# drive.net
KiCad netlist of a schematic drawn in Altium Designer
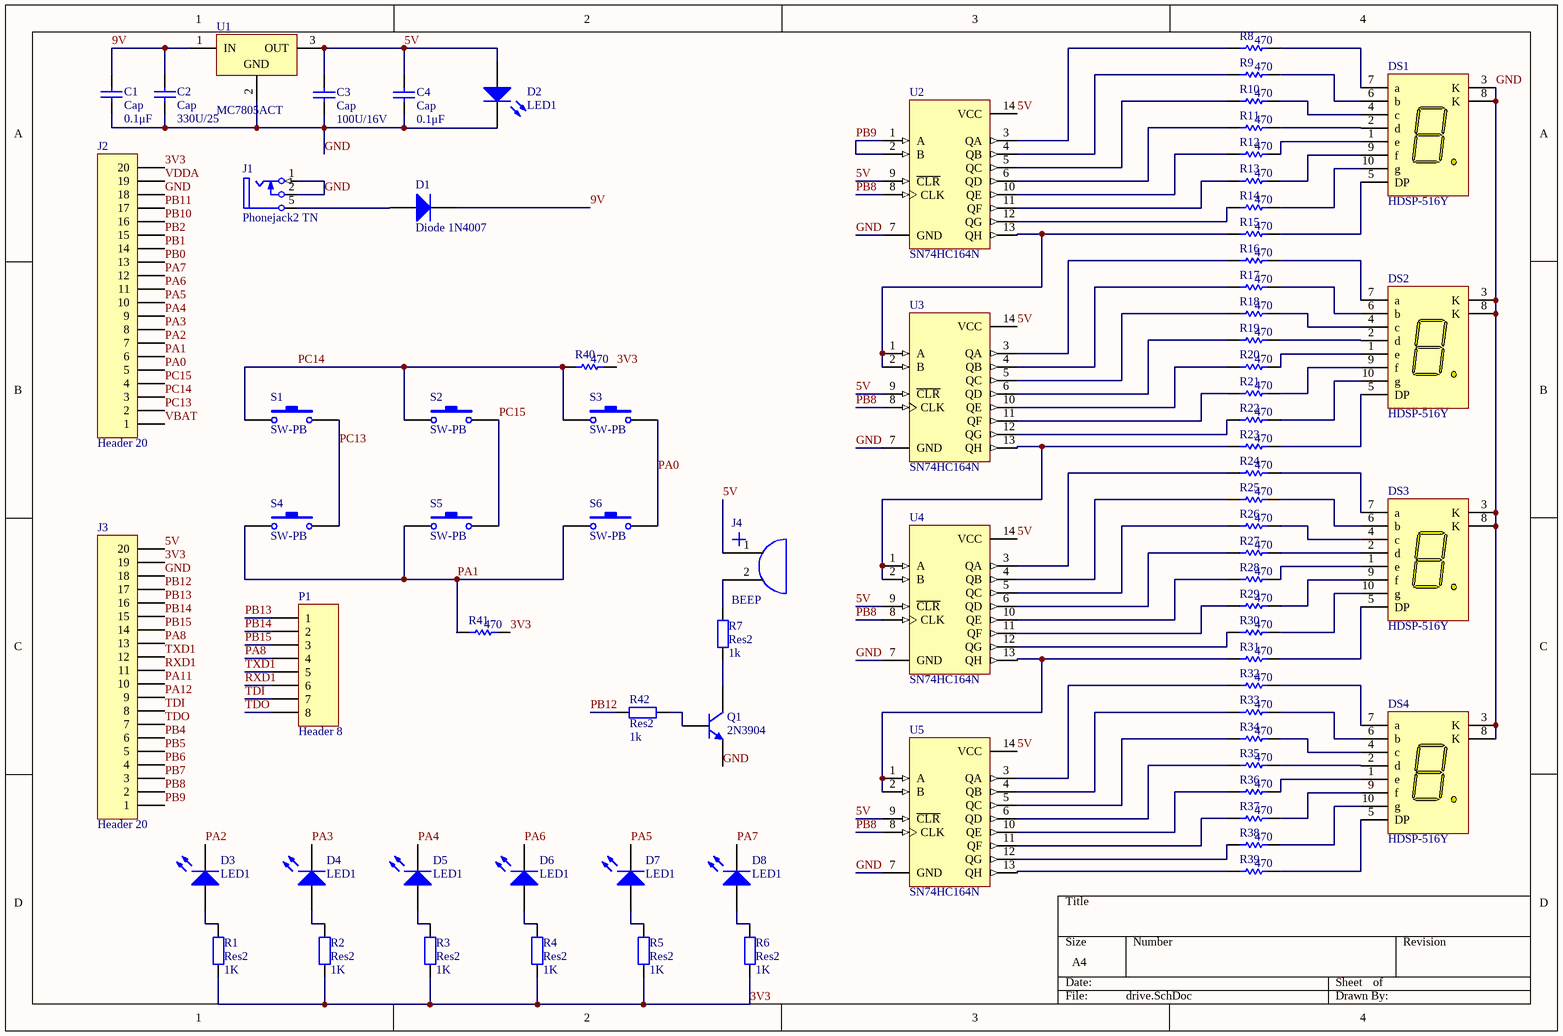
[diagram p0: drive.SchDoc]

(export (version "E")
  (design (tool "Eeschema 10.0.6"))
  (components
    (comp (ref "C1")
      (value "Cap")
      (footprint "RAD-0.3")
      (description "Capacitor")
      (fields (field (name "ALTIUM_VALUE") "0.1μF") (field (name "PUBLISHER") "Altium Limited"))
      (libsource (lib "Miscellaneous Devices") (part "Cap"))
    )
    (comp (ref "C2")
      (value "Cap")
      (footprint "RAD-0.3")
      (description "Capacitor")
      (fields (field (name "ALTIUM_VALUE") "330U/25") (field (name "PUBLISHER") "Altium Limited"))
      (libsource (lib "Miscellaneous Devices") (part "Cap"))
    )
    (comp (ref "C3")
      (value "Cap")
      (footprint "RAD-0.3")
      (description "Capacitor")
      (fields (field (name "ALTIUM_VALUE") "100U/16V") (field (name "PUBLISHER") "Altium Limited"))
      (libsource (lib "Miscellaneous Devices") (part "Cap"))
    )
    (comp (ref "C4")
      (value "Cap")
      (footprint "RAD-0.3")
      (description "Capacitor")
      (fields (field (name "ALTIUM_VALUE") "0.1μF") (field (name "PUBLISHER") "Altium Limited"))
      (libsource (lib "Miscellaneous Devices") (part "Cap"))
    )
    (comp (ref "D1")
      (value "Diode 1N4007")
      (footprint "DO-41")
      (description "1 Amp General Purpose Rectifier")
      (fields (field (name "PUBLISHER") "Altium Limited"))
      (libsource (lib "Miscellaneous Devices") (part "Diode 1N4007"))
    )
    (comp (ref "D2")
      (value "LED1")
      (footprint "LED-1")
      (description "Typical RED GaAs LED")
      (fields (field (name "PUBLISHER") "Altium Limited"))
      (libsource (lib "Miscellaneous Devices") (part "LED1"))
    )
    (comp (ref "D3")
      (value "LED1")
      (footprint "LED-1")
      (description "Typical RED GaAs LED")
      (fields (field (name "PUBLISHER") "Altium Limited"))
      (libsource (lib "Miscellaneous Devices") (part "LED1"))
    )
    (comp (ref "D4")
      (value "LED1")
      (footprint "LED-1")
      (description "Typical RED GaAs LED")
      (fields (field (name "PUBLISHER") "Altium Limited"))
      (libsource (lib "Miscellaneous Devices") (part "LED1"))
    )
    (comp (ref "D5")
      (value "LED1")
      (footprint "LED-1")
      (description "Typical RED GaAs LED")
      (fields (field (name "PUBLISHER") "Altium Limited"))
      (libsource (lib "Miscellaneous Devices") (part "LED1"))
    )
    (comp (ref "D6")
      (value "LED1")
      (footprint "LED-1")
      (description "Typical RED GaAs LED")
      (fields (field (name "PUBLISHER") "Altium Limited"))
      (libsource (lib "Miscellaneous Devices") (part "LED1"))
    )
    (comp (ref "D7")
      (value "LED1")
      (footprint "LED-1")
      (description "Typical RED GaAs LED")
      (fields (field (name "PUBLISHER") "Altium Limited"))
      (libsource (lib "Miscellaneous Devices") (part "LED1"))
    )
    (comp (ref "D8")
      (value "LED1")
      (footprint "LED-1")
      (description "Typical RED GaAs LED")
      (fields (field (name "PUBLISHER") "Altium Limited"))
      (libsource (lib "Miscellaneous Devices") (part "LED1"))
    )
    (comp (ref "DS1")
      (value "HDSP-516Y")
      (footprint "Case-5")
      (description "13 mm Slim Font, Standard Current, Yellow 7-Segment Display: CC, RH DP")
      (fields (field (name "PUBLISHER") "Altium Limited"))
      (libsource (lib "Agilent LED Display 7-Segment, 1-Digit") (part "HDSP-516Y"))
    )
    (comp (ref "DS2")
      (value "HDSP-516Y")
      (footprint "Case-5")
      (description "13 mm Slim Font, Standard Current, Yellow 7-Segment Display: CC, RH DP")
      (fields (field (name "PUBLISHER") "Altium Limited"))
      (libsource (lib "Agilent LED Display 7-Segment, 1-Digit") (part "HDSP-516Y"))
    )
    (comp (ref "DS3")
      (value "HDSP-516Y")
      (footprint "Case-5")
      (description "13 mm Slim Font, Standard Current, Yellow 7-Segment Display: CC, RH DP")
      (fields (field (name "PUBLISHER") "Altium Limited"))
      (libsource (lib "Agilent LED Display 7-Segment, 1-Digit") (part "HDSP-516Y"))
    )
    (comp (ref "DS4")
      (value "HDSP-516Y")
      (footprint "Case-5")
      (description "13 mm Slim Font, Standard Current, Yellow 7-Segment Display: CC, RH DP")
      (fields (field (name "PUBLISHER") "Altium Limited"))
      (libsource (lib "Agilent LED Display 7-Segment, 1-Digit") (part "HDSP-516Y"))
    )
    (comp (ref "J1")
      (value "Phonejack2 TN")
      (footprint "DC-005")
      (description "Jack Socket, 1/4\" [6.5mm], Thru-Hole, Vertical, 2-Conductor with Tip closed")
      (fields (field (name "PUBLISHER") "Altium Limited"))
      (libsource (lib "Miscellaneous Connectors") (part "Phonejack2 TN"))
    )
    (comp (ref "J2")
      (value "Header 20")
      (footprint "HDR1X20")
      (description "Header, 20-Pin")
      (fields (field (name "PUBLISHER") "Altium Limited"))
      (libsource (lib "Miscellaneous Connectors") (part "Header 20"))
    )
    (comp (ref "J3")
      (value "Header 20")
      (footprint "HDR1X20")
      (description "Header, 20-Pin")
      (fields (field (name "PUBLISHER") "Altium Limited"))
      (libsource (lib "Miscellaneous Connectors") (part "Header 20"))
    )
    (comp (ref "J4")
      (value "BEEP")
      (footprint "Beep")
      (description "蜂鸣器")
      (libsource (lib "TSLone") (part "BEEP"))
    )
    (comp (ref "P1")
      (value "Header 8")
      (footprint "HDR1X8")
      (description "Header, 8-Pin")
      (fields (field (name "PUBLISHER") "Altium Limited"))
      (libsource (lib "Miscellaneous Connectors") (part "Header 8"))
    )
    (comp (ref "Q1")
      (value "2N3904")
      (footprint "TO-92A")
      (description "NPN General Purpose Amplifier")
      (fields (field (name "PUBLISHER") "Altium Limited"))
      (libsource (lib "Miscellaneous Devices") (part "2N3904"))
    )
    (comp (ref "R1")
      (value "Res2")
      (footprint "AXIAL-0.4")
      (description "Resistor")
      (fields (field (name "ALTIUM_VALUE") "1K") (field (name "PUBLISHER") "Altium Limited"))
      (libsource (lib "Miscellaneous Devices") (part "Res2"))
    )
    (comp (ref "R2")
      (value "Res2")
      (footprint "AXIAL-0.4")
      (description "Resistor")
      (fields (field (name "ALTIUM_VALUE") "1K") (field (name "PUBLISHER") "Altium Limited"))
      (libsource (lib "Miscellaneous Devices") (part "Res2"))
    )
    (comp (ref "R3")
      (value "Res2")
      (footprint "AXIAL-0.4")
      (description "Resistor")
      (fields (field (name "ALTIUM_VALUE") "1K") (field (name "PUBLISHER") "Altium Limited"))
      (libsource (lib "Miscellaneous Devices") (part "Res2"))
    )
    (comp (ref "R4")
      (value "Res2")
      (footprint "AXIAL-0.4")
      (description "Resistor")
      (fields (field (name "ALTIUM_VALUE") "1K") (field (name "PUBLISHER") "Altium Limited"))
      (libsource (lib "Miscellaneous Devices") (part "Res2"))
    )
    (comp (ref "R5")
      (value "Res2")
      (footprint "AXIAL-0.4")
      (description "Resistor")
      (fields (field (name "ALTIUM_VALUE") "1K") (field (name "PUBLISHER") "Altium Limited"))
      (libsource (lib "Miscellaneous Devices") (part "Res2"))
    )
    (comp (ref "R6")
      (value "Res2")
      (footprint "AXIAL-0.4")
      (description "Resistor")
      (fields (field (name "ALTIUM_VALUE") "1K") (field (name "PUBLISHER") "Altium Limited"))
      (libsource (lib "Miscellaneous Devices") (part "Res2"))
    )
    (comp (ref "R7")
      (value "Res2")
      (footprint "AXIAL-0.4")
      (description "Resistor")
      (fields (field (name "ALTIUM_VALUE") "1k") (field (name "PUBLISHER") "Altium Limited"))
      (libsource (lib "Miscellaneous Devices") (part "Res2"))
    )
    (comp (ref "R8")
      (value "470")
      (footprint "AXIAL-0.3")
      (description "Resistor")
      (fields (field (name "Comment") "Res1") (field (name "PUBLISHER") "Altium Limited"))
      (libsource (lib "Miscellaneous Devices") (part "Res1"))
    )
    (comp (ref "R9")
      (value "470")
      (footprint "AXIAL-0.3")
      (description "Resistor")
      (fields (field (name "Comment") "Res1") (field (name "PUBLISHER") "Altium Limited"))
      (libsource (lib "Miscellaneous Devices") (part "Res1"))
    )
    (comp (ref "R10")
      (value "470")
      (footprint "AXIAL-0.3")
      (description "Resistor")
      (fields (field (name "Comment") "Res1") (field (name "PUBLISHER") "Altium Limited"))
      (libsource (lib "Miscellaneous Devices") (part "Res1"))
    )
    (comp (ref "R11")
      (value "470")
      (footprint "AXIAL-0.3")
      (description "Resistor")
      (fields (field (name "Comment") "Res1") (field (name "PUBLISHER") "Altium Limited"))
      (libsource (lib "Miscellaneous Devices") (part "Res1"))
    )
    (comp (ref "R12")
      (value "470")
      (footprint "AXIAL-0.3")
      (description "Resistor")
      (fields (field (name "Comment") "Res1") (field (name "PUBLISHER") "Altium Limited"))
      (libsource (lib "Miscellaneous Devices") (part "Res1"))
    )
    (comp (ref "R13")
      (value "470")
      (footprint "AXIAL-0.3")
      (description "Resistor")
      (fields (field (name "Comment") "Res1") (field (name "PUBLISHER") "Altium Limited"))
      (libsource (lib "Miscellaneous Devices") (part "Res1"))
    )
    (comp (ref "R14")
      (value "470")
      (footprint "AXIAL-0.3")
      (description "Resistor")
      (fields (field (name "Comment") "Res1") (field (name "PUBLISHER") "Altium Limited"))
      (libsource (lib "Miscellaneous Devices") (part "Res1"))
    )
    (comp (ref "R15")
      (value "470")
      (footprint "AXIAL-0.3")
      (description "Resistor")
      (fields (field (name "Comment") "Res1") (field (name "PUBLISHER") "Altium Limited"))
      (libsource (lib "Miscellaneous Devices") (part "Res1"))
    )
    (comp (ref "R16")
      (value "470")
      (footprint "AXIAL-0.3")
      (description "Resistor")
      (fields (field (name "Comment") "Res1") (field (name "PUBLISHER") "Altium Limited"))
      (libsource (lib "Miscellaneous Devices") (part "Res1"))
    )
    (comp (ref "R17")
      (value "470")
      (footprint "AXIAL-0.3")
      (description "Resistor")
      (fields (field (name "Comment") "Res1") (field (name "PUBLISHER") "Altium Limited"))
      (libsource (lib "Miscellaneous Devices") (part "Res1"))
    )
    (comp (ref "R18")
      (value "470")
      (footprint "AXIAL-0.3")
      (description "Resistor")
      (fields (field (name "Comment") "Res1") (field (name "PUBLISHER") "Altium Limited"))
      (libsource (lib "Miscellaneous Devices") (part "Res1"))
    )
    (comp (ref "R19")
      (value "470")
      (footprint "AXIAL-0.3")
      (description "Resistor")
      (fields (field (name "Comment") "Res1") (field (name "PUBLISHER") "Altium Limited"))
      (libsource (lib "Miscellaneous Devices") (part "Res1"))
    )
    (comp (ref "R20")
      (value "470")
      (footprint "AXIAL-0.3")
      (description "Resistor")
      (fields (field (name "Comment") "Res1") (field (name "PUBLISHER") "Altium Limited"))
      (libsource (lib "Miscellaneous Devices") (part "Res1"))
    )
    (comp (ref "R21")
      (value "470")
      (footprint "AXIAL-0.3")
      (description "Resistor")
      (fields (field (name "Comment") "Res1") (field (name "PUBLISHER") "Altium Limited"))
      (libsource (lib "Miscellaneous Devices") (part "Res1"))
    )
    (comp (ref "R22")
      (value "470")
      (footprint "AXIAL-0.3")
      (description "Resistor")
      (fields (field (name "Comment") "Res1") (field (name "PUBLISHER") "Altium Limited"))
      (libsource (lib "Miscellaneous Devices") (part "Res1"))
    )
    (comp (ref "R23")
      (value "470")
      (footprint "AXIAL-0.3")
      (description "Resistor")
      (fields (field (name "Comment") "Res1") (field (name "PUBLISHER") "Altium Limited"))
      (libsource (lib "Miscellaneous Devices") (part "Res1"))
    )
    (comp (ref "R24")
      (value "470")
      (footprint "AXIAL-0.3")
      (description "Resistor")
      (fields (field (name "Comment") "Res1") (field (name "PUBLISHER") "Altium Limited"))
      (libsource (lib "Miscellaneous Devices") (part "Res1"))
    )
    (comp (ref "R25")
      (value "470")
      (footprint "AXIAL-0.3")
      (description "Resistor")
      (fields (field (name "Comment") "Res1") (field (name "PUBLISHER") "Altium Limited"))
      (libsource (lib "Miscellaneous Devices") (part "Res1"))
    )
    (comp (ref "R26")
      (value "470")
      (footprint "AXIAL-0.3")
      (description "Resistor")
      (fields (field (name "Comment") "Res1") (field (name "PUBLISHER") "Altium Limited"))
      (libsource (lib "Miscellaneous Devices") (part "Res1"))
    )
    (comp (ref "R27")
      (value "470")
      (footprint "AXIAL-0.3")
      (description "Resistor")
      (fields (field (name "Comment") "Res1") (field (name "PUBLISHER") "Altium Limited"))
      (libsource (lib "Miscellaneous Devices") (part "Res1"))
    )
    (comp (ref "R28")
      (value "470")
      (footprint "AXIAL-0.3")
      (description "Resistor")
      (fields (field (name "Comment") "Res1") (field (name "PUBLISHER") "Altium Limited"))
      (libsource (lib "Miscellaneous Devices") (part "Res1"))
    )
    (comp (ref "R29")
      (value "470")
      (footprint "AXIAL-0.3")
      (description "Resistor")
      (fields (field (name "Comment") "Res1") (field (name "PUBLISHER") "Altium Limited"))
      (libsource (lib "Miscellaneous Devices") (part "Res1"))
    )
    (comp (ref "R30")
      (value "470")
      (footprint "AXIAL-0.3")
      (description "Resistor")
      (fields (field (name "Comment") "Res1") (field (name "PUBLISHER") "Altium Limited"))
      (libsource (lib "Miscellaneous Devices") (part "Res1"))
    )
    (comp (ref "R31")
      (value "470")
      (footprint "AXIAL-0.3")
      (description "Resistor")
      (fields (field (name "Comment") "Res1") (field (name "PUBLISHER") "Altium Limited"))
      (libsource (lib "Miscellaneous Devices") (part "Res1"))
    )
    (comp (ref "R32")
      (value "470")
      (footprint "AXIAL-0.3")
      (description "Resistor")
      (fields (field (name "Comment") "Res1") (field (name "PUBLISHER") "Altium Limited"))
      (libsource (lib "Miscellaneous Devices") (part "Res1"))
    )
    (comp (ref "R33")
      (value "470")
      (footprint "AXIAL-0.3")
      (description "Resistor")
      (fields (field (name "Comment") "Res1") (field (name "PUBLISHER") "Altium Limited"))
      (libsource (lib "Miscellaneous Devices") (part "Res1"))
    )
    (comp (ref "R34")
      (value "470")
      (footprint "AXIAL-0.3")
      (description "Resistor")
      (fields (field (name "Comment") "Res1") (field (name "PUBLISHER") "Altium Limited"))
      (libsource (lib "Miscellaneous Devices") (part "Res1"))
    )
    (comp (ref "R35")
      (value "470")
      (footprint "AXIAL-0.3")
      (description "Resistor")
      (fields (field (name "Comment") "Res1") (field (name "PUBLISHER") "Altium Limited"))
      (libsource (lib "Miscellaneous Devices") (part "Res1"))
    )
    (comp (ref "R36")
      (value "470")
      (footprint "AXIAL-0.3")
      (description "Resistor")
      (fields (field (name "Comment") "Res1") (field (name "PUBLISHER") "Altium Limited"))
      (libsource (lib "Miscellaneous Devices") (part "Res1"))
    )
    (comp (ref "R37")
      (value "470")
      (footprint "AXIAL-0.3")
      (description "Resistor")
      (fields (field (name "Comment") "Res1") (field (name "PUBLISHER") "Altium Limited"))
      (libsource (lib "Miscellaneous Devices") (part "Res1"))
    )
    (comp (ref "R38")
      (value "470")
      (footprint "AXIAL-0.3")
      (description "Resistor")
      (fields (field (name "Comment") "Res1") (field (name "PUBLISHER") "Altium Limited"))
      (libsource (lib "Miscellaneous Devices") (part "Res1"))
    )
    (comp (ref "R39")
      (value "470")
      (footprint "AXIAL-0.3")
      (description "Resistor")
      (fields (field (name "Comment") "Res1") (field (name "PUBLISHER") "Altium Limited"))
      (libsource (lib "Miscellaneous Devices") (part "Res1"))
    )
    (comp (ref "R40")
      (value "470")
      (footprint "AXIAL-0.3")
      (description "Resistor")
      (fields (field (name "Comment") "Res1") (field (name "PUBLISHER") "Altium Limited"))
      (libsource (lib "Miscellaneous Devices") (part "Res1"))
    )
    (comp (ref "R41")
      (value "470")
      (footprint "AXIAL-0.3")
      (description "Resistor")
      (fields (field (name "Comment") "Res1") (field (name "PUBLISHER") "Altium Limited"))
      (libsource (lib "Miscellaneous Devices") (part "Res1"))
    )
    (comp (ref "R42")
      (value "Res2")
      (footprint "AXIAL-0.4")
      (description "Resistor")
      (fields (field (name "ALTIUM_VALUE") "1k") (field (name "PUBLISHER") "Altium Limited"))
      (libsource (lib "") (part "Res2_1"))
    )
    (comp (ref "S1")
      (value "SW-PB")
      (footprint "SW9")
      (description "微动开关")
      (fields (field (name "PUBLISHER") "Altium Limited"))
      (libsource (lib "TSLone") (part "SW-PB"))
    )
    (comp (ref "S2")
      (value "SW-PB")
      (footprint "SW9")
      (description "微动开关")
      (fields (field (name "PUBLISHER") "Altium Limited"))
      (libsource (lib "TSLone") (part "SW-PB"))
    )
    (comp (ref "S3")
      (value "SW-PB")
      (footprint "SW9")
      (description "微动开关")
      (fields (field (name "PUBLISHER") "Altium Limited"))
      (libsource (lib "TSLone") (part "SW-PB"))
    )
    (comp (ref "S4")
      (value "SW-PB")
      (footprint "SW9")
      (description "微动开关")
      (fields (field (name "PUBLISHER") "Altium Limited"))
      (libsource (lib "TSLone") (part "SW-PB"))
    )
    (comp (ref "S5")
      (value "SW-PB")
      (footprint "SW9")
      (description "微动开关")
      (fields (field (name "PUBLISHER") "Altium Limited"))
      (libsource (lib "TSLone") (part "SW-PB"))
    )
    (comp (ref "S6")
      (value "SW-PB")
      (footprint "SW9")
      (description "微动开关")
      (fields (field (name "PUBLISHER") "Altium Limited"))
      (libsource (lib "TSLone") (part "SW-PB"))
    )
    (comp (ref "U1")
      (value "MC7805ACT")
      (footprint "221A-06")
      (description "Three-Terminal Positive Voltage Regulator")
      (fields (field (name "PUBLISHER") "Altium Limited"))
      (libsource (lib "ON Semi Power Mgt Voltage Regulator") (part "MC7805ACT"))
    )
    (comp (ref "U2")
      (value "SN74HC164N")
      (footprint "N014")
      (description "8-Bit Parallel-Out Serial Shift Register")
      (fields (field (name "PUBLISHER") "Altium Limited"))
      (libsource (lib "TI Logic Register") (part "SN74HC164N"))
    )
    (comp (ref "U3")
      (value "SN74HC164N")
      (footprint "N014")
      (description "8-Bit Parallel-Out Serial Shift Register")
      (fields (field (name "PUBLISHER") "Altium Limited"))
      (libsource (lib "TI Logic Register") (part "SN74HC164N"))
    )
    (comp (ref "U4")
      (value "SN74HC164N")
      (footprint "N014")
      (description "8-Bit Parallel-Out Serial Shift Register")
      (fields (field (name "PUBLISHER") "Altium Limited"))
      (libsource (lib "TI Logic Register") (part "SN74HC164N"))
    )
    (comp (ref "U5")
      (value "SN74HC164N")
      (footprint "N014")
      (description "8-Bit Parallel-Out Serial Shift Register")
      (fields (field (name "PUBLISHER") "Altium Limited"))
      (libsource (lib "TI Logic Register") (part "SN74HC164N"))
    )
  )
  (nets
    (net (code "1") (name "/3V3") (class "Default")
      (node (ref "J2") (pin "20") (pinfunction "20_20") (pintype "passive"))
      (node (ref "J3") (pin "19") (pinfunction "19_19") (pintype "passive"))
      (node (ref "R1") (pin "1") (pinfunction "1_1") (pintype "passive"))
      (node (ref "R2") (pin "1") (pinfunction "1_1") (pintype "passive"))
      (node (ref "R3") (pin "1") (pinfunction "1_1") (pintype "passive"))
      (node (ref "R4") (pin "1") (pinfunction "1_1") (pintype "passive"))
      (node (ref "R40") (pin "2") (pinfunction "2_2") (pintype "passive"))
      (node (ref "R41") (pin "2") (pinfunction "2_2") (pintype "passive"))
      (node (ref "R5") (pin "1") (pinfunction "1_1") (pintype "passive"))
      (node (ref "R6") (pin "1") (pinfunction "1_1") (pintype "passive"))
    )
    (net (code "2") (name "/5V") (class "Default")
      (node (ref "C3") (pin "1") (pinfunction "1_1") (pintype "passive"))
      (node (ref "C4") (pin "1") (pinfunction "1_1") (pintype "passive"))
      (node (ref "D2") (pin "1") (pinfunction "A_1") (pintype "passive"))
      (node (ref "J3") (pin "20") (pinfunction "20_20") (pintype "passive"))
      (node (ref "J4") (pin "1") (pinfunction "0_1") (pintype "passive"))
      (node (ref "U1") (pin "3") (pinfunction "OUT_3") (pintype "power_in"))
      (node (ref "U2") (pin "14") (pinfunction "VCC_14") (pintype "power_in"))
      (node (ref "U2") (pin "9") (pinfunction "~{CLR}_9") (pintype "input"))
      (node (ref "U3") (pin "14") (pinfunction "VCC_14") (pintype "power_in"))
      (node (ref "U3") (pin "9") (pinfunction "~{CLR}_9") (pintype "input"))
      (node (ref "U4") (pin "14") (pinfunction "VCC_14") (pintype "power_in"))
      (node (ref "U4") (pin "9") (pinfunction "~{CLR}_9") (pintype "input"))
      (node (ref "U5") (pin "14") (pinfunction "VCC_14") (pintype "power_in"))
      (node (ref "U5") (pin "9") (pinfunction "~{CLR}_9") (pintype "input"))
    )
    (net (code "3") (name "/9V") (class "Default")
      (node (ref "C1") (pin "1") (pinfunction "1_1") (pintype "passive"))
      (node (ref "C2") (pin "1") (pinfunction "1_1") (pintype "passive"))
      (node (ref "D1") (pin "2") (pinfunction "K_2") (pintype "passive"))
      (node (ref "U1") (pin "1") (pinfunction "IN_1") (pintype "power_in"))
    )
    (net (code "4") (name "/GND") (class "Default")
      (node (ref "C1") (pin "2") (pinfunction "2_2") (pintype "passive"))
      (node (ref "C2") (pin "2") (pinfunction "2_2") (pintype "passive"))
      (node (ref "C3") (pin "2") (pinfunction "2_2") (pintype "passive"))
      (node (ref "C4") (pin "2") (pinfunction "2_2") (pintype "passive"))
      (node (ref "D2") (pin "2") (pinfunction "K_2") (pintype "passive"))
      (node (ref "DS1") (pin "3") (pinfunction "K_3") (pintype "passive"))
      (node (ref "DS1") (pin "8") (pinfunction "K_8") (pintype "passive"))
      (node (ref "DS2") (pin "3") (pinfunction "K_3") (pintype "passive"))
      (node (ref "DS2") (pin "8") (pinfunction "K_8") (pintype "passive"))
      (node (ref "DS3") (pin "3") (pinfunction "K_3") (pintype "passive"))
      (node (ref "DS3") (pin "8") (pinfunction "K_8") (pintype "passive"))
      (node (ref "DS4") (pin "3") (pinfunction "K_3") (pintype "passive"))
      (node (ref "DS4") (pin "8") (pinfunction "K_8") (pintype "passive"))
      (node (ref "J1") (pin "1") (pinfunction "T_1") (pintype "input"))
      (node (ref "J1") (pin "2") (pinfunction "TN_2") (pintype "passive"))
      (node (ref "J2") (pin "18") (pinfunction "18_18") (pintype "passive"))
      (node (ref "J3") (pin "18") (pinfunction "18_18") (pintype "passive"))
      (node (ref "Q1") (pin "1") (pinfunction "E_1") (pintype "passive"))
      (node (ref "U1") (pin "2") (pinfunction "GND_2") (pintype "power_in"))
      (node (ref "U2") (pin "7") (pinfunction "GND_7") (pintype "power_in"))
      (node (ref "U3") (pin "7") (pinfunction "GND_7") (pintype "power_in"))
      (node (ref "U4") (pin "7") (pinfunction "GND_7") (pintype "power_in"))
      (node (ref "U5") (pin "7") (pinfunction "GND_7") (pintype "power_in"))
    )
    (net (code "5") (name "/PA0") (class "Default")
      (node (ref "J2") (pin "5") (pinfunction "5_5") (pintype "passive"))
      (node (ref "S3") (pin "2") (pinfunction "2_2") (pintype "passive"))
      (node (ref "S6") (pin "2") (pinfunction "2_2") (pintype "passive"))
    )
    (net (code "6") (name "/PA1") (class "Default")
      (node (ref "J2") (pin "6") (pinfunction "6_6") (pintype "passive"))
      (node (ref "R41") (pin "1") (pinfunction "1_1") (pintype "passive"))
      (node (ref "S4") (pin "1") (pinfunction "1_1") (pintype "passive"))
      (node (ref "S5") (pin "1") (pinfunction "1_1") (pintype "passive"))
      (node (ref "S6") (pin "1") (pinfunction "1_1") (pintype "passive"))
    )
    (net (code "7") (name "/PA2") (class "Default")
      (node (ref "D3") (pin "2") (pinfunction "K_2") (pintype "passive"))
      (node (ref "J2") (pin "7") (pinfunction "7_7") (pintype "passive"))
    )
    (net (code "8") (name "/PA3") (class "Default")
      (node (ref "D4") (pin "2") (pinfunction "K_2") (pintype "passive"))
      (node (ref "J2") (pin "8") (pinfunction "8_8") (pintype "passive"))
    )
    (net (code "9") (name "/PA4") (class "Default")
      (node (ref "D5") (pin "2") (pinfunction "K_2") (pintype "passive"))
      (node (ref "J2") (pin "9") (pinfunction "9_9") (pintype "passive"))
    )
    (net (code "10") (name "/PA5") (class "Default")
      (node (ref "D7") (pin "2") (pinfunction "K_2") (pintype "passive"))
      (node (ref "J2") (pin "10") (pinfunction "10_10") (pintype "passive"))
    )
    (net (code "11") (name "/PA6") (class "Default")
      (node (ref "D6") (pin "2") (pinfunction "K_2") (pintype "passive"))
      (node (ref "J2") (pin "11") (pinfunction "11_11") (pintype "passive"))
    )
    (net (code "12") (name "/PA7") (class "Default")
      (node (ref "D8") (pin "2") (pinfunction "K_2") (pintype "passive"))
      (node (ref "J2") (pin "12") (pinfunction "12_12") (pintype "passive"))
    )
    (net (code "13") (name "/PA8") (class "Default")
      (node (ref "J3") (pin "13") (pinfunction "13_13") (pintype "passive"))
      (node (ref "P1") (pin "4") (pinfunction "4_4") (pintype "passive"))
    )
    (net (code "14") (name "/PA11") (class "Default")
      (node (ref "J3") (pin "10") (pinfunction "10_10") (pintype "passive"))
    )
    (net (code "15") (name "/PA12") (class "Default")
      (node (ref "J3") (pin "9") (pinfunction "9_9") (pintype "passive"))
    )
    (net (code "16") (name "/PB0") (class "Default")
      (node (ref "J2") (pin "13") (pinfunction "13_13") (pintype "passive"))
    )
    (net (code "17") (name "/PB1") (class "Default")
      (node (ref "J2") (pin "14") (pinfunction "14_14") (pintype "passive"))
    )
    (net (code "18") (name "/PB2") (class "Default")
      (node (ref "J2") (pin "15") (pinfunction "15_15") (pintype "passive"))
    )
    (net (code "19") (name "/PB4") (class "Default")
      (node (ref "J3") (pin "6") (pinfunction "6_6") (pintype "passive"))
    )
    (net (code "20") (name "/PB5") (class "Default")
      (node (ref "J3") (pin "5") (pinfunction "5_5") (pintype "passive"))
    )
    (net (code "21") (name "/PB6") (class "Default")
      (node (ref "J3") (pin "4") (pinfunction "4_4") (pintype "passive"))
    )
    (net (code "22") (name "/PB7") (class "Default")
      (node (ref "J3") (pin "3") (pinfunction "3_3") (pintype "passive"))
    )
    (net (code "23") (name "/PB8") (class "Default")
      (node (ref "J3") (pin "2") (pinfunction "2_2") (pintype "passive"))
      (node (ref "U2") (pin "8") (pinfunction "CLK_8") (pintype "input"))
      (node (ref "U3") (pin "8") (pinfunction "CLK_8") (pintype "input"))
      (node (ref "U4") (pin "8") (pinfunction "CLK_8") (pintype "input"))
      (node (ref "U5") (pin "8") (pinfunction "CLK_8") (pintype "input"))
    )
    (net (code "24") (name "/PB9") (class "Default")
      (node (ref "J3") (pin "1") (pinfunction "1_1") (pintype "passive"))
      (node (ref "U2") (pin "1") (pinfunction "A_1") (pintype "input"))
      (node (ref "U2") (pin "2") (pinfunction "B_2") (pintype "input"))
    )
    (net (code "25") (name "/PB10") (class "Default")
      (node (ref "J2") (pin "16") (pinfunction "16_16") (pintype "passive"))
    )
    (net (code "26") (name "/PB11") (class "Default")
      (node (ref "J2") (pin "17") (pinfunction "17_17") (pintype "passive"))
    )
    (net (code "27") (name "/PB12") (class "Default")
      (node (ref "J3") (pin "17") (pinfunction "17_17") (pintype "passive"))
      (node (ref "R42") (pin "2") (pinfunction "2_2") (pintype "passive"))
    )
    (net (code "28") (name "/PB13") (class "Default")
      (node (ref "J3") (pin "16") (pinfunction "16_16") (pintype "passive"))
      (node (ref "P1") (pin "1") (pinfunction "1_1") (pintype "passive"))
    )
    (net (code "29") (name "/PB14") (class "Default")
      (node (ref "J3") (pin "15") (pinfunction "15_15") (pintype "passive"))
      (node (ref "P1") (pin "2") (pinfunction "2_2") (pintype "passive"))
    )
    (net (code "30") (name "/PB15") (class "Default")
      (node (ref "J3") (pin "14") (pinfunction "14_14") (pintype "passive"))
      (node (ref "P1") (pin "3") (pinfunction "3_3") (pintype "passive"))
    )
    (net (code "31") (name "/PC13") (class "Default")
      (node (ref "J2") (pin "2") (pinfunction "2_2") (pintype "passive"))
      (node (ref "S1") (pin "2") (pinfunction "2_2") (pintype "passive"))
      (node (ref "S4") (pin "2") (pinfunction "2_2") (pintype "passive"))
    )
    (net (code "32") (name "/PC14") (class "Default")
      (node (ref "J2") (pin "3") (pinfunction "3_3") (pintype "passive"))
      (node (ref "R40") (pin "1") (pinfunction "1_1") (pintype "passive"))
      (node (ref "S1") (pin "1") (pinfunction "1_1") (pintype "passive"))
      (node (ref "S2") (pin "1") (pinfunction "1_1") (pintype "passive"))
      (node (ref "S3") (pin "1") (pinfunction "1_1") (pintype "passive"))
    )
    (net (code "33") (name "/PC15") (class "Default")
      (node (ref "J2") (pin "4") (pinfunction "4_4") (pintype "passive"))
      (node (ref "S2") (pin "2") (pinfunction "2_2") (pintype "passive"))
      (node (ref "S5") (pin "2") (pinfunction "2_2") (pintype "passive"))
    )
    (net (code "34") (name "/RXD1") (class "Default")
      (node (ref "J3") (pin "11") (pinfunction "11_11") (pintype "passive"))
      (node (ref "P1") (pin "6") (pinfunction "6_6") (pintype "passive"))
    )
    (net (code "35") (name "/TDI") (class "Default")
      (node (ref "J3") (pin "8") (pinfunction "8_8") (pintype "passive"))
      (node (ref "P1") (pin "7") (pinfunction "7_7") (pintype "passive"))
    )
    (net (code "36") (name "/TDO") (class "Default")
      (node (ref "J3") (pin "7") (pinfunction "7_7") (pintype "passive"))
      (node (ref "P1") (pin "8") (pinfunction "8_8") (pintype "passive"))
    )
    (net (code "37") (name "/TXD1") (class "Default")
      (node (ref "J3") (pin "12") (pinfunction "12_12") (pintype "passive"))
      (node (ref "P1") (pin "5") (pinfunction "5_5") (pintype "passive"))
    )
    (net (code "38") (name "/VBAT") (class "Default")
      (node (ref "J2") (pin "1") (pinfunction "1_1") (pintype "passive"))
    )
    (net (code "39") (name "/VDDA") (class "Default")
      (node (ref "J2") (pin "19") (pinfunction "19_19") (pintype "passive"))
    )
    (net (code "40") (name "Net-(D1-A)") (class "Default")
      (node (ref "D1") (pin "1") (pinfunction "A_1") (pintype "passive"))
      (node (ref "J1") (pin "5") (pinfunction "S_5") (pintype "power_in"))
    )
    (net (code "41") (name "Net-(D3-A)") (class "Default")
      (node (ref "D3") (pin "1") (pinfunction "A_1") (pintype "passive"))
      (node (ref "R1") (pin "2") (pinfunction "2_2") (pintype "passive"))
    )
    (net (code "42") (name "Net-(D4-A)") (class "Default")
      (node (ref "D4") (pin "1") (pinfunction "A_1") (pintype "passive"))
      (node (ref "R2") (pin "2") (pinfunction "2_2") (pintype "passive"))
    )
    (net (code "43") (name "Net-(D5-A)") (class "Default")
      (node (ref "D5") (pin "1") (pinfunction "A_1") (pintype "passive"))
      (node (ref "R3") (pin "2") (pinfunction "2_2") (pintype "passive"))
    )
    (net (code "44") (name "Net-(D6-A)") (class "Default")
      (node (ref "D6") (pin "1") (pinfunction "A_1") (pintype "passive"))
      (node (ref "R4") (pin "2") (pinfunction "2_2") (pintype "passive"))
    )
    (net (code "45") (name "Net-(D7-A)") (class "Default")
      (node (ref "D7") (pin "1") (pinfunction "A_1") (pintype "passive"))
      (node (ref "R5") (pin "2") (pinfunction "2_2") (pintype "passive"))
    )
    (net (code "46") (name "Net-(D8-A)") (class "Default")
      (node (ref "D8") (pin "1") (pinfunction "A_1") (pintype "passive"))
      (node (ref "R6") (pin "2") (pinfunction "2_2") (pintype "passive"))
    )
    (net (code "47") (name "Net-(DS1-DP)") (class "Default")
      (node (ref "DS1") (pin "5") (pinfunction "DP_5") (pintype "passive"))
      (node (ref "R15") (pin "2") (pinfunction "2_2") (pintype "passive"))
    )
    (net (code "48") (name "Net-(DS1-a)") (class "Default")
      (node (ref "DS1") (pin "7") (pinfunction "a_7") (pintype "passive"))
      (node (ref "R8") (pin "2") (pinfunction "2_2") (pintype "passive"))
    )
    (net (code "49") (name "Net-(DS1-b)") (class "Default")
      (node (ref "DS1") (pin "6") (pinfunction "b_6") (pintype "passive"))
      (node (ref "R9") (pin "2") (pinfunction "2_2") (pintype "passive"))
    )
    (net (code "50") (name "Net-(DS1-c)") (class "Default")
      (node (ref "DS1") (pin "4") (pinfunction "c_4") (pintype "passive"))
      (node (ref "R10") (pin "2") (pinfunction "2_2") (pintype "passive"))
    )
    (net (code "51") (name "Net-(DS1-d)") (class "Default")
      (node (ref "DS1") (pin "2") (pinfunction "d_2") (pintype "passive"))
      (node (ref "R11") (pin "2") (pinfunction "2_2") (pintype "passive"))
    )
    (net (code "52") (name "Net-(DS1-e)") (class "Default")
      (node (ref "DS1") (pin "1") (pinfunction "e_1") (pintype "passive"))
      (node (ref "R12") (pin "2") (pinfunction "2_2") (pintype "passive"))
    )
    (net (code "53") (name "Net-(DS1-f)") (class "Default")
      (node (ref "DS1") (pin "9") (pinfunction "f_9") (pintype "passive"))
      (node (ref "R13") (pin "2") (pinfunction "2_2") (pintype "passive"))
    )
    (net (code "54") (name "Net-(DS1-g)") (class "Default")
      (node (ref "DS1") (pin "10") (pinfunction "g_10") (pintype "passive"))
      (node (ref "R14") (pin "2") (pinfunction "2_2") (pintype "passive"))
    )
    (net (code "55") (name "Net-(DS2-DP)") (class "Default")
      (node (ref "DS2") (pin "5") (pinfunction "DP_5") (pintype "passive"))
      (node (ref "R23") (pin "2") (pinfunction "2_2") (pintype "passive"))
    )
    (net (code "56") (name "Net-(DS2-a)") (class "Default")
      (node (ref "DS2") (pin "7") (pinfunction "a_7") (pintype "passive"))
      (node (ref "R16") (pin "2") (pinfunction "2_2") (pintype "passive"))
    )
    (net (code "57") (name "Net-(DS2-b)") (class "Default")
      (node (ref "DS2") (pin "6") (pinfunction "b_6") (pintype "passive"))
      (node (ref "R17") (pin "2") (pinfunction "2_2") (pintype "passive"))
    )
    (net (code "58") (name "Net-(DS2-c)") (class "Default")
      (node (ref "DS2") (pin "4") (pinfunction "c_4") (pintype "passive"))
      (node (ref "R18") (pin "2") (pinfunction "2_2") (pintype "passive"))
    )
    (net (code "59") (name "Net-(DS2-d)") (class "Default")
      (node (ref "DS2") (pin "2") (pinfunction "d_2") (pintype "passive"))
      (node (ref "R19") (pin "2") (pinfunction "2_2") (pintype "passive"))
    )
    (net (code "60") (name "Net-(DS2-e)") (class "Default")
      (node (ref "DS2") (pin "1") (pinfunction "e_1") (pintype "passive"))
      (node (ref "R20") (pin "2") (pinfunction "2_2") (pintype "passive"))
    )
    (net (code "61") (name "Net-(DS2-f)") (class "Default")
      (node (ref "DS2") (pin "9") (pinfunction "f_9") (pintype "passive"))
      (node (ref "R21") (pin "2") (pinfunction "2_2") (pintype "passive"))
    )
    (net (code "62") (name "Net-(DS2-g)") (class "Default")
      (node (ref "DS2") (pin "10") (pinfunction "g_10") (pintype "passive"))
      (node (ref "R22") (pin "2") (pinfunction "2_2") (pintype "passive"))
    )
    (net (code "63") (name "Net-(DS3-DP)") (class "Default")
      (node (ref "DS3") (pin "5") (pinfunction "DP_5") (pintype "passive"))
      (node (ref "R31") (pin "2") (pinfunction "2_2") (pintype "passive"))
    )
    (net (code "64") (name "Net-(DS3-a)") (class "Default")
      (node (ref "DS3") (pin "7") (pinfunction "a_7") (pintype "passive"))
      (node (ref "R24") (pin "2") (pinfunction "2_2") (pintype "passive"))
    )
    (net (code "65") (name "Net-(DS3-b)") (class "Default")
      (node (ref "DS3") (pin "6") (pinfunction "b_6") (pintype "passive"))
      (node (ref "R25") (pin "2") (pinfunction "2_2") (pintype "passive"))
    )
    (net (code "66") (name "Net-(DS3-c)") (class "Default")
      (node (ref "DS3") (pin "4") (pinfunction "c_4") (pintype "passive"))
      (node (ref "R26") (pin "2") (pinfunction "2_2") (pintype "passive"))
    )
    (net (code "67") (name "Net-(DS3-d)") (class "Default")
      (node (ref "DS3") (pin "2") (pinfunction "d_2") (pintype "passive"))
      (node (ref "R27") (pin "2") (pinfunction "2_2") (pintype "passive"))
    )
    (net (code "68") (name "Net-(DS3-e)") (class "Default")
      (node (ref "DS3") (pin "1") (pinfunction "e_1") (pintype "passive"))
      (node (ref "R28") (pin "2") (pinfunction "2_2") (pintype "passive"))
    )
    (net (code "69") (name "Net-(DS3-f)") (class "Default")
      (node (ref "DS3") (pin "9") (pinfunction "f_9") (pintype "passive"))
      (node (ref "R29") (pin "2") (pinfunction "2_2") (pintype "passive"))
    )
    (net (code "70") (name "Net-(DS3-g)") (class "Default")
      (node (ref "DS3") (pin "10") (pinfunction "g_10") (pintype "passive"))
      (node (ref "R30") (pin "2") (pinfunction "2_2") (pintype "passive"))
    )
    (net (code "71") (name "Net-(DS4-DP)") (class "Default")
      (node (ref "DS4") (pin "5") (pinfunction "DP_5") (pintype "passive"))
      (node (ref "R39") (pin "2") (pinfunction "2_2") (pintype "passive"))
    )
    (net (code "72") (name "Net-(DS4-a)") (class "Default")
      (node (ref "DS4") (pin "7") (pinfunction "a_7") (pintype "passive"))
      (node (ref "R32") (pin "2") (pinfunction "2_2") (pintype "passive"))
    )
    (net (code "73") (name "Net-(DS4-b)") (class "Default")
      (node (ref "DS4") (pin "6") (pinfunction "b_6") (pintype "passive"))
      (node (ref "R33") (pin "2") (pinfunction "2_2") (pintype "passive"))
    )
    (net (code "74") (name "Net-(DS4-c)") (class "Default")
      (node (ref "DS4") (pin "4") (pinfunction "c_4") (pintype "passive"))
      (node (ref "R34") (pin "2") (pinfunction "2_2") (pintype "passive"))
    )
    (net (code "75") (name "Net-(DS4-d)") (class "Default")
      (node (ref "DS4") (pin "2") (pinfunction "d_2") (pintype "passive"))
      (node (ref "R35") (pin "2") (pinfunction "2_2") (pintype "passive"))
    )
    (net (code "76") (name "Net-(DS4-e)") (class "Default")
      (node (ref "DS4") (pin "1") (pinfunction "e_1") (pintype "passive"))
      (node (ref "R36") (pin "2") (pinfunction "2_2") (pintype "passive"))
    )
    (net (code "77") (name "Net-(DS4-f)") (class "Default")
      (node (ref "DS4") (pin "9") (pinfunction "f_9") (pintype "passive"))
      (node (ref "R37") (pin "2") (pinfunction "2_2") (pintype "passive"))
    )
    (net (code "78") (name "Net-(DS4-g)") (class "Default")
      (node (ref "DS4") (pin "10") (pinfunction "g_10") (pintype "passive"))
      (node (ref "R38") (pin "2") (pinfunction "2_2") (pintype "passive"))
    )
    (net (code "79") (name "Net-(J4-1)") (class "Default")
      (node (ref "J4") (pin "2") (pinfunction "1_2") (pintype "passive"))
      (node (ref "R7") (pin "2") (pinfunction "2_2") (pintype "passive"))
    )
    (net (code "80") (name "Net-(Q1-B)") (class "Default")
      (node (ref "Q1") (pin "2") (pinfunction "B_2") (pintype "passive"))
      (node (ref "R42") (pin "1") (pinfunction "1_1") (pintype "passive"))
    )
    (net (code "81") (name "Net-(Q1-C)") (class "Default")
      (node (ref "Q1") (pin "3") (pinfunction "C_3") (pintype "passive"))
      (node (ref "R7") (pin "1") (pinfunction "1_1") (pintype "passive"))
    )
    (net (code "82") (name "Net-(U2-QA)") (class "Default")
      (node (ref "R8") (pin "1") (pinfunction "1_1") (pintype "passive"))
      (node (ref "U2") (pin "3") (pinfunction "QA_3") (pintype "output"))
    )
    (net (code "83") (name "Net-(U2-QB)") (class "Default")
      (node (ref "R9") (pin "1") (pinfunction "1_1") (pintype "passive"))
      (node (ref "U2") (pin "4") (pinfunction "QB_4") (pintype "output"))
    )
    (net (code "84") (name "Net-(U2-QC)") (class "Default")
      (node (ref "R10") (pin "1") (pinfunction "1_1") (pintype "passive"))
      (node (ref "U2") (pin "5") (pinfunction "QC_5") (pintype "output"))
    )
    (net (code "85") (name "Net-(U2-QD)") (class "Default")
      (node (ref "R11") (pin "1") (pinfunction "1_1") (pintype "passive"))
      (node (ref "U2") (pin "6") (pinfunction "QD_6") (pintype "output"))
    )
    (net (code "86") (name "Net-(U2-QE)") (class "Default")
      (node (ref "R12") (pin "1") (pinfunction "1_1") (pintype "passive"))
      (node (ref "U2") (pin "10") (pinfunction "QE_10") (pintype "output"))
    )
    (net (code "87") (name "Net-(U2-QF)") (class "Default")
      (node (ref "R13") (pin "1") (pinfunction "1_1") (pintype "passive"))
      (node (ref "U2") (pin "11") (pinfunction "QF_11") (pintype "output"))
    )
    (net (code "88") (name "Net-(U2-QG)") (class "Default")
      (node (ref "R14") (pin "1") (pinfunction "1_1") (pintype "passive"))
      (node (ref "U2") (pin "12") (pinfunction "QG_12") (pintype "output"))
    )
    (net (code "89") (name "Net-(U2-QH)") (class "Default")
      (node (ref "R15") (pin "1") (pinfunction "1_1") (pintype "passive"))
      (node (ref "U2") (pin "13") (pinfunction "QH_13") (pintype "output"))
      (node (ref "U3") (pin "1") (pinfunction "A_1") (pintype "input"))
      (node (ref "U3") (pin "2") (pinfunction "B_2") (pintype "input"))
    )
    (net (code "90") (name "Net-(U3-QA)") (class "Default")
      (node (ref "R16") (pin "1") (pinfunction "1_1") (pintype "passive"))
      (node (ref "U3") (pin "3") (pinfunction "QA_3") (pintype "output"))
    )
    (net (code "91") (name "Net-(U3-QB)") (class "Default")
      (node (ref "R17") (pin "1") (pinfunction "1_1") (pintype "passive"))
      (node (ref "U3") (pin "4") (pinfunction "QB_4") (pintype "output"))
    )
    (net (code "92") (name "Net-(U3-QC)") (class "Default")
      (node (ref "R18") (pin "1") (pinfunction "1_1") (pintype "passive"))
      (node (ref "U3") (pin "5") (pinfunction "QC_5") (pintype "output"))
    )
    (net (code "93") (name "Net-(U3-QD)") (class "Default")
      (node (ref "R19") (pin "1") (pinfunction "1_1") (pintype "passive"))
      (node (ref "U3") (pin "6") (pinfunction "QD_6") (pintype "output"))
    )
    (net (code "94") (name "Net-(U3-QE)") (class "Default")
      (node (ref "R20") (pin "1") (pinfunction "1_1") (pintype "passive"))
      (node (ref "U3") (pin "10") (pinfunction "QE_10") (pintype "output"))
    )
    (net (code "95") (name "Net-(U3-QF)") (class "Default")
      (node (ref "R21") (pin "1") (pinfunction "1_1") (pintype "passive"))
      (node (ref "U3") (pin "11") (pinfunction "QF_11") (pintype "output"))
    )
    (net (code "96") (name "Net-(U3-QG)") (class "Default")
      (node (ref "R22") (pin "1") (pinfunction "1_1") (pintype "passive"))
      (node (ref "U3") (pin "12") (pinfunction "QG_12") (pintype "output"))
    )
    (net (code "97") (name "Net-(U3-QH)") (class "Default")
      (node (ref "R23") (pin "1") (pinfunction "1_1") (pintype "passive"))
      (node (ref "U3") (pin "13") (pinfunction "QH_13") (pintype "output"))
      (node (ref "U4") (pin "1") (pinfunction "A_1") (pintype "input"))
      (node (ref "U4") (pin "2") (pinfunction "B_2") (pintype "input"))
    )
    (net (code "98") (name "Net-(U4-QA)") (class "Default")
      (node (ref "R24") (pin "1") (pinfunction "1_1") (pintype "passive"))
      (node (ref "U4") (pin "3") (pinfunction "QA_3") (pintype "output"))
    )
    (net (code "99") (name "Net-(U4-QB)") (class "Default")
      (node (ref "R25") (pin "1") (pinfunction "1_1") (pintype "passive"))
      (node (ref "U4") (pin "4") (pinfunction "QB_4") (pintype "output"))
    )
    (net (code "100") (name "Net-(U4-QC)") (class "Default")
      (node (ref "R26") (pin "1") (pinfunction "1_1") (pintype "passive"))
      (node (ref "U4") (pin "5") (pinfunction "QC_5") (pintype "output"))
    )
    (net (code "101") (name "Net-(U4-QD)") (class "Default")
      (node (ref "R27") (pin "1") (pinfunction "1_1") (pintype "passive"))
      (node (ref "U4") (pin "6") (pinfunction "QD_6") (pintype "output"))
    )
    (net (code "102") (name "Net-(U4-QE)") (class "Default")
      (node (ref "R28") (pin "1") (pinfunction "1_1") (pintype "passive"))
      (node (ref "U4") (pin "10") (pinfunction "QE_10") (pintype "output"))
    )
    (net (code "103") (name "Net-(U4-QF)") (class "Default")
      (node (ref "R29") (pin "1") (pinfunction "1_1") (pintype "passive"))
      (node (ref "U4") (pin "11") (pinfunction "QF_11") (pintype "output"))
    )
    (net (code "104") (name "Net-(U4-QG)") (class "Default")
      (node (ref "R30") (pin "1") (pinfunction "1_1") (pintype "passive"))
      (node (ref "U4") (pin "12") (pinfunction "QG_12") (pintype "output"))
    )
    (net (code "105") (name "Net-(U4-QH)") (class "Default")
      (node (ref "R31") (pin "1") (pinfunction "1_1") (pintype "passive"))
      (node (ref "U4") (pin "13") (pinfunction "QH_13") (pintype "output"))
      (node (ref "U5") (pin "1") (pinfunction "A_1") (pintype "input"))
      (node (ref "U5") (pin "2") (pinfunction "B_2") (pintype "input"))
    )
    (net (code "106") (name "Net-(U5-QA)") (class "Default")
      (node (ref "R32") (pin "1") (pinfunction "1_1") (pintype "passive"))
      (node (ref "U5") (pin "3") (pinfunction "QA_3") (pintype "output"))
    )
    (net (code "107") (name "Net-(U5-QB)") (class "Default")
      (node (ref "R33") (pin "1") (pinfunction "1_1") (pintype "passive"))
      (node (ref "U5") (pin "4") (pinfunction "QB_4") (pintype "output"))
    )
    (net (code "108") (name "Net-(U5-QC)") (class "Default")
      (node (ref "R34") (pin "1") (pinfunction "1_1") (pintype "passive"))
      (node (ref "U5") (pin "5") (pinfunction "QC_5") (pintype "output"))
    )
    (net (code "109") (name "Net-(U5-QD)") (class "Default")
      (node (ref "R35") (pin "1") (pinfunction "1_1") (pintype "passive"))
      (node (ref "U5") (pin "6") (pinfunction "QD_6") (pintype "output"))
    )
    (net (code "110") (name "Net-(U5-QE)") (class "Default")
      (node (ref "R36") (pin "1") (pinfunction "1_1") (pintype "passive"))
      (node (ref "U5") (pin "10") (pinfunction "QE_10") (pintype "output"))
    )
    (net (code "111") (name "Net-(U5-QF)") (class "Default")
      (node (ref "R37") (pin "1") (pinfunction "1_1") (pintype "passive"))
      (node (ref "U5") (pin "11") (pinfunction "QF_11") (pintype "output"))
    )
    (net (code "112") (name "Net-(U5-QG)") (class "Default")
      (node (ref "R38") (pin "1") (pinfunction "1_1") (pintype "passive"))
      (node (ref "U5") (pin "12") (pinfunction "QG_12") (pintype "output"))
    )
    (net (code "113") (name "Net-(U5-QH)") (class "Default")
      (node (ref "R39") (pin "1") (pinfunction "1_1") (pintype "passive"))
      (node (ref "U5") (pin "13") (pinfunction "QH_13") (pintype "output"))
    )
  )
)
